# TrinketBlinkM0D.net
KiCad netlist of a schematic drawn in EAGLE
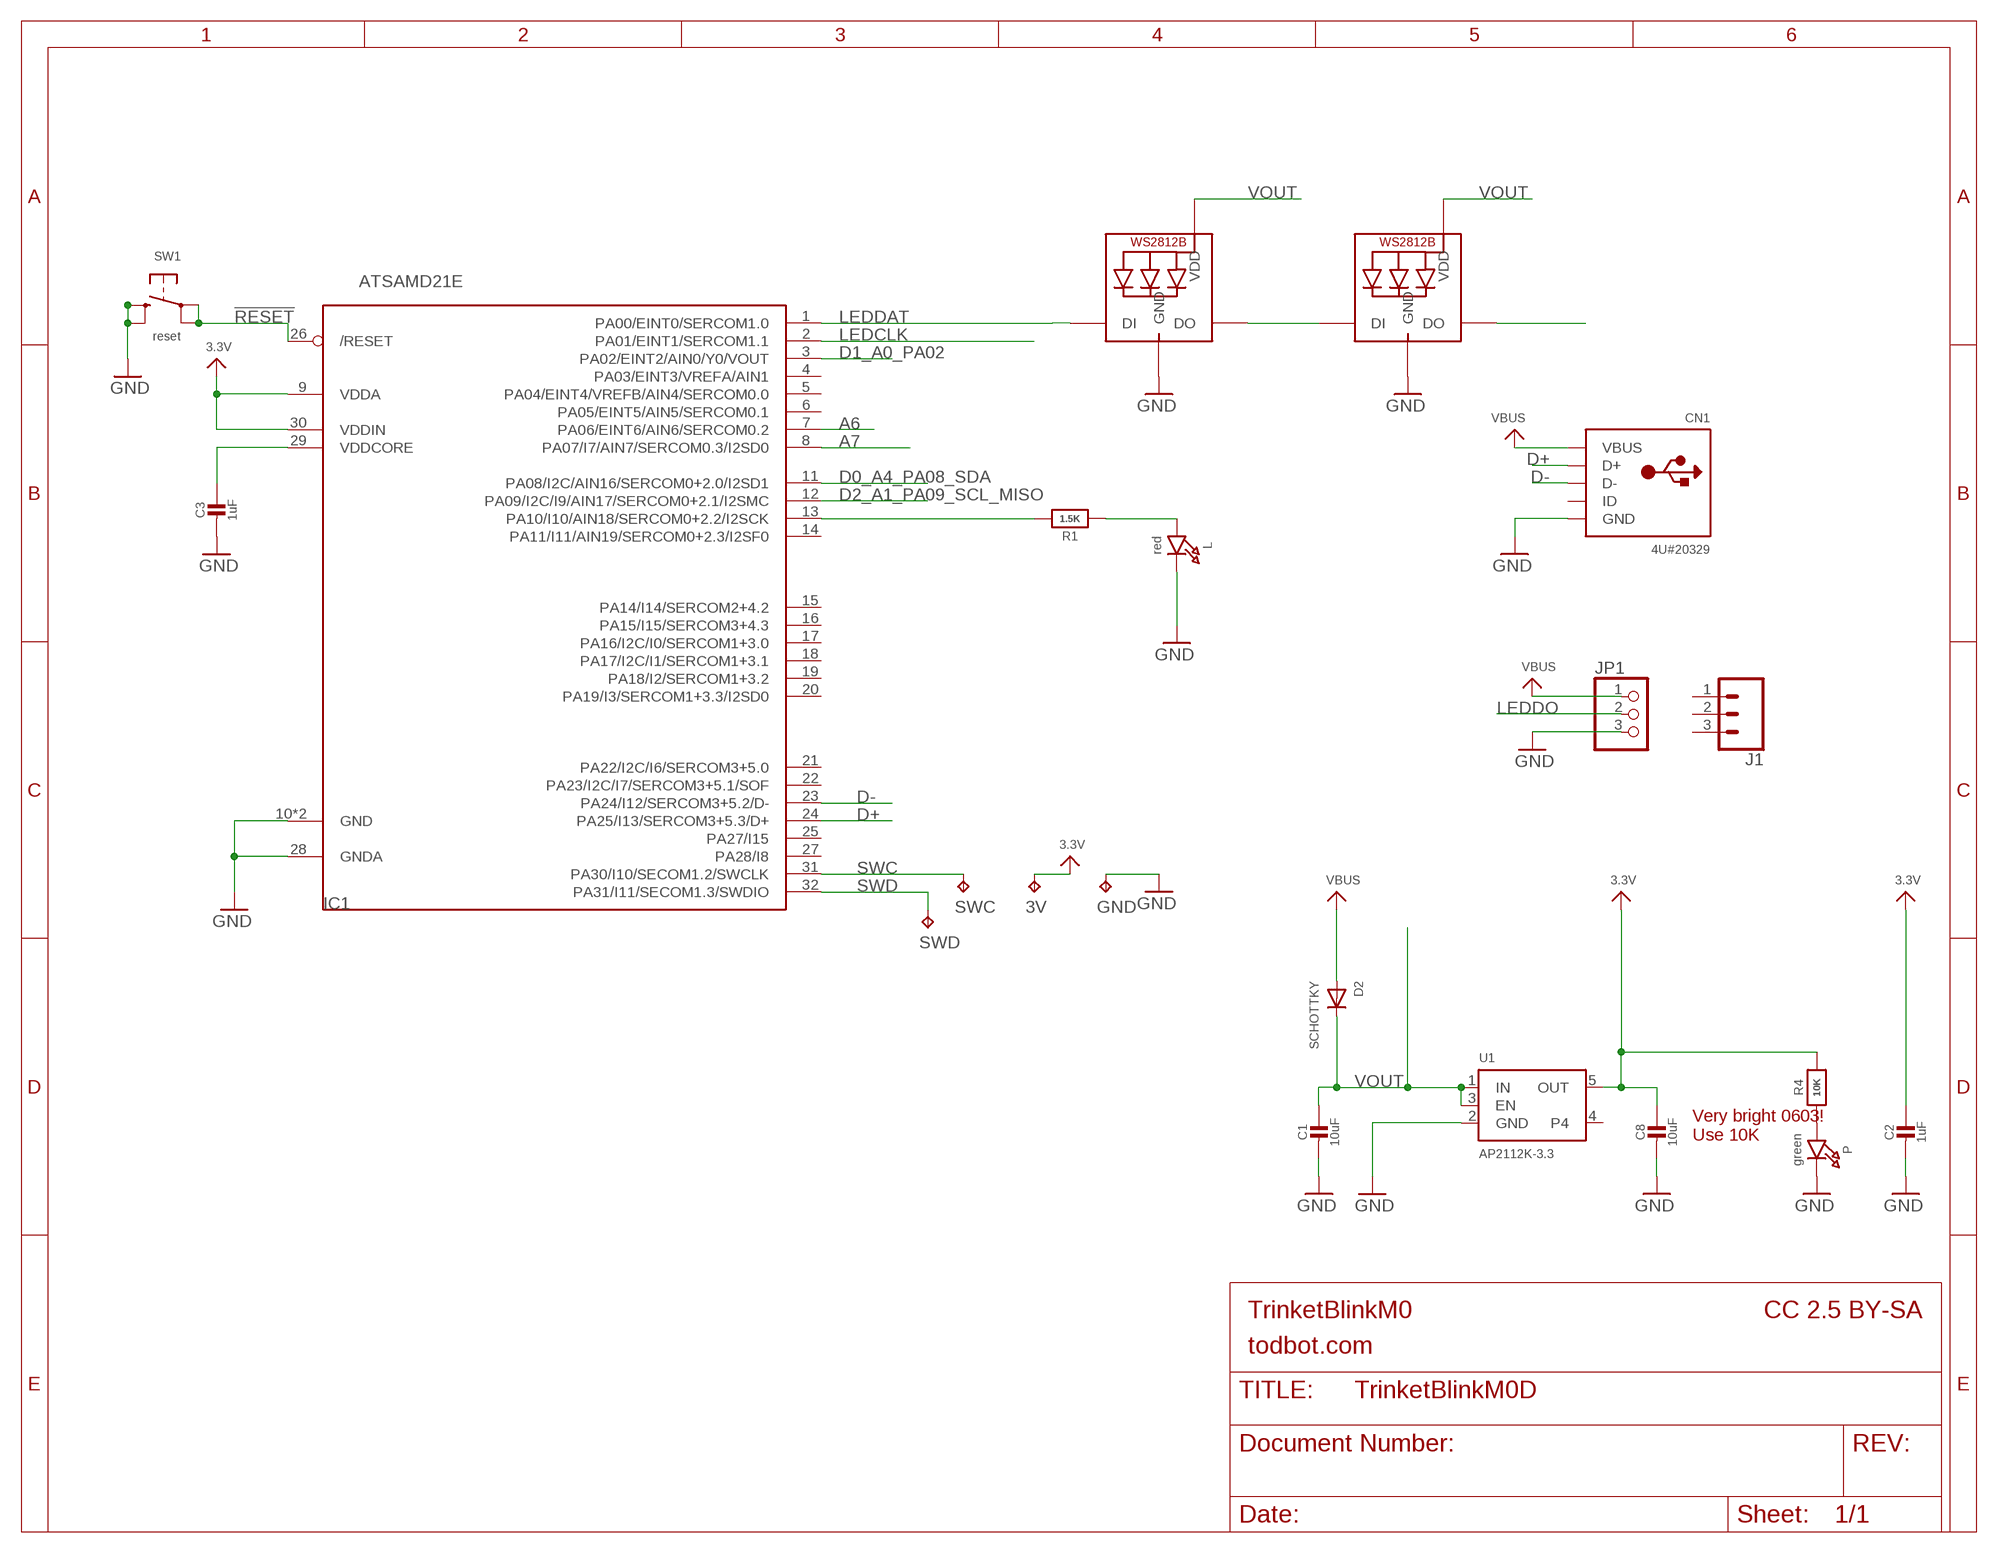
[diagram p0: schematic, sheet 1]

(export (version "E")
  (design (tool "Eeschema 10.0.6"))
  (components
    (comp (ref "3V")
      (value "TPB1,27")
      (footprint "eagle-import:B1,27")
      (libsource (lib "eagle-import") (part "TPB1,27"))
    )
    (comp (ref "C1")
      (value "10uF")
      (footprint "eagle-import:0805-NO")
      (libsource (lib "eagle-import") (part "CAP_CERAMIC0805-NOOUTLINE"))
    )
    (comp (ref "C2")
      (value "1uF")
      (footprint "eagle-import:0603-NO")
      (libsource (lib "eagle-import") (part "CAP_CERAMIC0603_NO"))
    )
    (comp (ref "C3")
      (value "1uF")
      (footprint "eagle-import:0603-NO")
      (libsource (lib "eagle-import") (part "CAP_CERAMIC0603_NO"))
    )
    (comp (ref "C8")
      (value "10uF")
      (footprint "eagle-import:0805-NO")
      (libsource (lib "eagle-import") (part "CAP_CERAMIC0805-NOOUTLINE"))
    )
    (comp (ref "CN1")
      (value "4U#20329")
      (footprint "eagle-import:4UCONN_20329_V2")
      (libsource (lib "eagle-import") (part "USB_MICRO_20329_V2"))
    )
    (comp (ref "D2")
      (value "SCHOTTKY")
      (footprint "eagle-import:SOD-123FL")
      (libsource (lib "eagle-import") (part "DIODE_SOD-123FL"))
    )
    (comp (ref "GND")
      (value "TPB1,27")
      (footprint "eagle-import:B1,27")
      (libsource (lib "eagle-import") (part "TPB1,27"))
    )
    (comp (ref "IC1")
      (value "ATSAMD21E")
      (footprint "eagle-import:QFN32_5MM")
      (libsource (lib "eagle-import") (part "ATSAMD21E"))
    )
    (comp (ref "J1")
      (value "CONN_03LONGPADS")
      (footprint "eagle-import:1X03_LONGPADS")
      (libsource (lib "eagle-import") (part "CONN_03LONGPADS"))
    )
    (comp (ref "JP1")
      (value "PINHD-1X3CB")
      (footprint "eagle-import:1X03-CLEANBIG")
      (libsource (lib "eagle-import") (part "PINHD-1X3CB"))
    )
    (comp (ref "L")
      (value "red")
      (footprint "eagle-import:CHIPLED_0603_NOOUTLINE")
      (libsource (lib "eagle-import") (part "LED0603_NOOUTLINE"))
    )
    (comp (ref "LED1")
      (value "WS2812B_5050N")
      (footprint "eagle-import:WS2812B-NARROW")
      (libsource (lib "eagle-import") (part "WS2812B_5050N"))
    )
    (comp (ref "LED2")
      (value "WS2812B_5050N")
      (footprint "eagle-import:WS2812B-NARROW")
      (libsource (lib "eagle-import") (part "WS2812B_5050N"))
    )
    (comp (ref "P")
      (value "green")
      (footprint "eagle-import:CHIPLED_0603_NOOUTLINE")
      (libsource (lib "eagle-import") (part "LED0603_NOOUTLINE"))
    )
    (comp (ref "R1")
      (value "1.5K")
      (footprint "eagle-import:0603-NO")
      (libsource (lib "eagle-import") (part "RESISTOR_0603_NOOUT"))
    )
    (comp (ref "R4")
      (value "10K")
      (footprint "eagle-import:0603-NO")
      (libsource (lib "eagle-import") (part "RESISTOR_0603_NOOUT"))
    )
    (comp (ref "SW1")
      (value "reset")
      (footprint "eagle-import:BTN_KMR2_4.6X2.8")
      (libsource (lib "eagle-import") (part "SWITCH_TACT_SMT4.6X2.8"))
    )
    (comp (ref "SWC")
      (value "TPB1,27")
      (footprint "eagle-import:B1,27")
      (libsource (lib "eagle-import") (part "TPB1,27"))
    )
    (comp (ref "SWD")
      (value "TPB1,27")
      (footprint "eagle-import:B1,27")
      (libsource (lib "eagle-import") (part "TPB1,27"))
    )
    (comp (ref "U1")
      (value "AP2112K-3.3")
      (footprint "eagle-import:SOT23-5")
      (libsource (lib "eagle-import") (part "VREG_SOT23-5"))
    )
  )
  (nets
    (net (code "1") (name "/A6") (class "Default")
      (node (ref "IC1") (pin "7") (pinfunction "PA06/EINT6/AIN6/SERCOM0.2_7") (pintype "bidirectional"))
    )
    (net (code "2") (name "/A7") (class "Default")
      (node (ref "IC1") (pin "8") (pinfunction "PA07/I7/AIN7/SERCOM0.3/I2SD0_8") (pintype "bidirectional"))
    )
    (net (code "3") (name "/D+") (class "Default")
      (node (ref "CN1") (pin "D+") (pinfunction "D+_D+") (pintype "bidirectional"))
      (node (ref "IC1") (pin "24") (pinfunction "PA25/I13/SERCOM3+5.3/D+_24") (pintype "bidirectional"))
    )
    (net (code "4") (name "/D-") (class "Default")
      (node (ref "CN1") (pin "D-") (pinfunction "D-_D-") (pintype "bidirectional"))
      (node (ref "IC1") (pin "23") (pinfunction "PA24/I12/SERCOM3+5.2/D-_23") (pintype "bidirectional"))
    )
    (net (code "5") (name "/D0_A4_PA08_SDA") (class "Default")
      (node (ref "IC1") (pin "11") (pinfunction "PA08/I2C/AIN16/SERCOM0+2.0/I2SD1_11") (pintype "bidirectional"))
    )
    (net (code "6") (name "/D1_A0_PA02") (class "Default")
      (node (ref "IC1") (pin "3") (pinfunction "PA02/EINT2/AIN0/Y0/VOUT_3") (pintype "bidirectional"))
    )
    (net (code "7") (name "/D2_A1_PA09_SCL_MISO") (class "Default")
      (node (ref "IC1") (pin "12") (pinfunction "PA09/I2C/I9/AIN17/SERCOM0+2.1/I2SMC_12") (pintype "bidirectional"))
    )
    (net (code "8") (name "/LEDCLK") (class "Default")
      (node (ref "IC1") (pin "2") (pinfunction "PA01/EINT1/SERCOM1.1_2") (pintype "bidirectional"))
    )
    (net (code "9") (name "/LEDDAT") (class "Default")
      (node (ref "IC1") (pin "1") (pinfunction "PA00/EINT0/SERCOM1.0_1") (pintype "bidirectional"))
      (node (ref "LED1") (pin "4-DIN") (pinfunction "DI_4-DIN") (pintype "input"))
    )
    (net (code "10") (name "/LEDDO") (class "Default")
      (node (ref "JP1") (pin "2") (pinfunction "2_2") (pintype "passive"))
      (node (ref "LED2") (pin "2-DOUT") (pinfunction "DO_2-DOUT") (pintype "output"))
    )
    (net (code "11") (name "/SWC") (class "Default")
      (node (ref "IC1") (pin "31") (pinfunction "PA30/I10/SECOM1.2/SWCLK_31") (pintype "bidirectional"))
      (node (ref "SWC") (pin "TP") (pinfunction "TP_TP") (pintype "input"))
    )
    (net (code "12") (name "/SWD") (class "Default")
      (node (ref "IC1") (pin "32") (pinfunction "PA31/I11/SECOM1.3/SWDIO_32") (pintype "bidirectional"))
      (node (ref "SWD") (pin "TP") (pinfunction "TP_TP") (pintype "input"))
    )
    (net (code "13") (name "/VOUT") (class "Default")
      (node (ref "C1") (pin "1") (pinfunction "1_1") (pintype "passive"))
      (node (ref "D2") (pin "C") (pinfunction "C_C") (pintype "passive"))
      (node (ref "LED1") (pin "1-VDD") (pinfunction "VDD_1-VDD") (pintype "power_in"))
      (node (ref "LED2") (pin "1-VDD") (pinfunction "VDD_1-VDD") (pintype "power_in"))
      (node (ref "U1") (pin "1") (pinfunction "IN_1") (pintype "power_in"))
      (node (ref "U1") (pin "3") (pinfunction "EN_3") (pintype "input"))
    )
    (net (code "14") (name "/~{RESET}") (class "Default")
      (node (ref "IC1") (pin "26") (pinfunction "/RESET_26") (pintype "bidirectional"))
      (node (ref "SW1") (pin "A") (pinfunction "P_A") (pintype "passive"))
      (node (ref "SW1") (pin "A'") (pinfunction "P1_A'") (pintype "passive"))
    )
    (net (code "15") (name "3.3V") (class "Default")
      (node (ref "3V") (pin "TP") (pinfunction "TP_TP") (pintype "input"))
      (node (ref "C2") (pin "1") (pinfunction "1_1") (pintype "passive"))
      (node (ref "C8") (pin "1") (pinfunction "1_1") (pintype "passive"))
      (node (ref "IC1") (pin "30") (pinfunction "VDDIN_30") (pintype "power_in"))
      (node (ref "IC1") (pin "9") (pinfunction "VDDA_9") (pintype "power_in"))
      (node (ref "R4") (pin "2") (pinfunction "2_2") (pintype "passive"))
      (node (ref "U1") (pin "5") (pinfunction "OUT_5") (pintype "power_in"))
    )
    (net (code "16") (name "GND") (class "Default")
      (node (ref "C1") (pin "2") (pinfunction "2_2") (pintype "passive"))
      (node (ref "C2") (pin "2") (pinfunction "2_2") (pintype "passive"))
      (node (ref "C3") (pin "2") (pinfunction "2_2") (pintype "passive"))
      (node (ref "C8") (pin "2") (pinfunction "2_2") (pintype "passive"))
      (node (ref "CN1") (pin "BASE@1") (pinfunction "GND_BASE@1") (pintype "power_in"))
      (node (ref "CN1") (pin "BASE@2") (pinfunction "GND_BASE@2") (pintype "power_in"))
      (node (ref "CN1") (pin "GND") (pinfunction "GND_GND") (pintype "power_in"))
      (node (ref "CN1") (pin "SPRT@1") (pinfunction "GND_SPRT@1") (pintype "power_in"))
      (node (ref "CN1") (pin "SPRT@2") (pinfunction "GND_SPRT@2") (pintype "power_in"))
      (node (ref "CN1") (pin "SPRT@3") (pinfunction "GND_SPRT@3") (pintype "power_in"))
      (node (ref "CN1") (pin "SPRT@4") (pinfunction "GND_SPRT@4") (pintype "power_in"))
      (node (ref "GND") (pin "TP") (pinfunction "TP_TP") (pintype "input"))
      (node (ref "IC1") (pin "10") (pinfunction "GND_10") (pintype "power_in"))
      (node (ref "IC1") (pin "28") (pinfunction "GNDA_28") (pintype "power_in"))
      (node (ref "IC1") (pin "33") (pinfunction "GND_33") (pintype "power_in"))
      (node (ref "JP1") (pin "3") (pinfunction "3_3") (pintype "passive"))
      (node (ref "L") (pin "C") (pinfunction "C_C") (pintype "passive"))
      (node (ref "LED1") (pin "3-GND") (pinfunction "GND_3-GND") (pintype "power_in"))
      (node (ref "LED2") (pin "3-GND") (pinfunction "GND_3-GND") (pintype "power_in"))
      (node (ref "P") (pin "C") (pinfunction "C_C") (pintype "passive"))
      (node (ref "SW1") (pin "B") (pinfunction "S_B") (pintype "passive"))
      (node (ref "SW1") (pin "B'") (pinfunction "S1_B'") (pintype "passive"))
      (node (ref "U1") (pin "2") (pinfunction "GND_2") (pintype "power_in"))
    )
    (net (code "17") (name "Net-(IC1-PA10{slash}I10{slash}AIN18{slash}SERCOM0+2.2{slash}I2SCK)") (class "Default")
      (node (ref "IC1") (pin "13") (pinfunction "PA10/I10/AIN18/SERCOM0+2.2/I2SCK_13") (pintype "bidirectional"))
      (node (ref "R1") (pin "2") (pinfunction "2_2") (pintype "passive"))
    )
    (net (code "18") (name "Net-(IC1-VDDCORE)") (class "Default")
      (node (ref "C3") (pin "1") (pinfunction "1_1") (pintype "passive"))
      (node (ref "IC1") (pin "29") (pinfunction "VDDCORE_29") (pintype "power_in"))
    )
    (net (code "19") (name "Net-(L-PadA)") (class "Default")
      (node (ref "L") (pin "A") (pinfunction "A_A") (pintype "passive"))
      (node (ref "R1") (pin "1") (pinfunction "1_1") (pintype "passive"))
    )
    (net (code "20") (name "Net-(LED1-DO)") (class "Default")
      (node (ref "LED1") (pin "2-DOUT") (pinfunction "DO_2-DOUT") (pintype "output"))
      (node (ref "LED2") (pin "4-DIN") (pinfunction "DI_4-DIN") (pintype "input"))
    )
    (net (code "21") (name "Net-(P-PadA)") (class "Default")
      (node (ref "P") (pin "A") (pinfunction "A_A") (pintype "passive"))
      (node (ref "R4") (pin "1") (pinfunction "1_1") (pintype "passive"))
    )
    (net (code "22") (name "VBUS") (class "Default")
      (node (ref "CN1") (pin "VBUS") (pinfunction "VBUS_VBUS") (pintype "power_in"))
      (node (ref "D2") (pin "A") (pinfunction "A_A") (pintype "passive"))
      (node (ref "JP1") (pin "1") (pinfunction "1_1") (pintype "passive"))
    )
    (net (code "23") (name "unconnected-(CN1-PadID)") (class "Default")
      (node (ref "CN1") (pin "ID") (pinfunction "ID_ID") (pintype "bidirectional"))
    )
    (net (code "24") (name "unconnected-(IC1-PA03{slash}EINT3{slash}VREFA{slash}AIN1-Pad4)") (class "Default")
      (node (ref "IC1") (pin "4") (pinfunction "PA03/EINT3/VREFA/AIN1_4") (pintype "bidirectional"))
    )
    (net (code "25") (name "unconnected-(IC1-PA04{slash}EINT4{slash}VREFB{slash}AIN4{slash}SERCOM0.0-Pad5)") (class "Default")
      (node (ref "IC1") (pin "5") (pinfunction "PA04/EINT4/VREFB/AIN4/SERCOM0.0_5") (pintype "bidirectional"))
    )
    (net (code "26") (name "unconnected-(IC1-PA05{slash}EINT5{slash}AIN5{slash}SERCOM0.1-Pad6)") (class "Default")
      (node (ref "IC1") (pin "6") (pinfunction "PA05/EINT5/AIN5/SERCOM0.1_6") (pintype "bidirectional"))
    )
    (net (code "27") (name "unconnected-(IC1-PA11{slash}I11{slash}AIN19{slash}SERCOM0+2.3{slash}I2SF0-Pad14)") (class "Default")
      (node (ref "IC1") (pin "14") (pinfunction "PA11/I11/AIN19/SERCOM0+2.3/I2SF0_14") (pintype "bidirectional"))
    )
    (net (code "28") (name "unconnected-(IC1-PA14{slash}I14{slash}SERCOM2+4.2-Pad15)") (class "Default")
      (node (ref "IC1") (pin "15") (pinfunction "PA14/I14/SERCOM2+4.2_15") (pintype "bidirectional"))
    )
    (net (code "29") (name "unconnected-(IC1-PA15{slash}I15{slash}SERCOM3+4.3-Pad16)") (class "Default")
      (node (ref "IC1") (pin "16") (pinfunction "PA15/I15/SERCOM3+4.3_16") (pintype "bidirectional"))
    )
    (net (code "30") (name "unconnected-(IC1-PA16{slash}I2C{slash}I0{slash}SERCOM1+3.0-Pad17)") (class "Default")
      (node (ref "IC1") (pin "17") (pinfunction "PA16/I2C/I0/SERCOM1+3.0_17") (pintype "bidirectional"))
    )
    (net (code "31") (name "unconnected-(IC1-PA17{slash}I2C{slash}I1{slash}SERCOM1+3.1-Pad18)") (class "Default")
      (node (ref "IC1") (pin "18") (pinfunction "PA17/I2C/I1/SERCOM1+3.1_18") (pintype "bidirectional"))
    )
    (net (code "32") (name "unconnected-(IC1-PA18{slash}I2{slash}SERCOM1+3.2-Pad19)") (class "Default")
      (node (ref "IC1") (pin "19") (pinfunction "PA18/I2/SERCOM1+3.2_19") (pintype "bidirectional"))
    )
    (net (code "33") (name "unconnected-(IC1-PA19{slash}I3{slash}SERCOM1+3.3{slash}I2SD0-Pad20)") (class "Default")
      (node (ref "IC1") (pin "20") (pinfunction "PA19/I3/SERCOM1+3.3/I2SD0_20") (pintype "bidirectional"))
    )
    (net (code "34") (name "unconnected-(IC1-PA22{slash}I2C{slash}I6{slash}SERCOM3+5.0-Pad21)") (class "Default")
      (node (ref "IC1") (pin "21") (pinfunction "PA22/I2C/I6/SERCOM3+5.0_21") (pintype "bidirectional"))
    )
    (net (code "35") (name "unconnected-(IC1-PA23{slash}I2C{slash}I7{slash}SERCOM3+5.1{slash}SOF-Pad22)") (class "Default")
      (node (ref "IC1") (pin "22") (pinfunction "PA23/I2C/I7/SERCOM3+5.1/SOF_22") (pintype "bidirectional"))
    )
    (net (code "36") (name "unconnected-(IC1-PA27{slash}I15-Pad25)") (class "Default")
      (node (ref "IC1") (pin "25") (pinfunction "PA27/I15_25") (pintype "bidirectional"))
    )
    (net (code "37") (name "unconnected-(IC1-PA28{slash}I8-Pad27)") (class "Default")
      (node (ref "IC1") (pin "27") (pinfunction "PA28/I8_27") (pintype "bidirectional"))
    )
    (net (code "38") (name "unconnected-(J1-Pad1)") (class "Default")
      (node (ref "J1") (pin "1") (pinfunction "1_1") (pintype "passive"))
    )
    (net (code "39") (name "unconnected-(J1-Pad2)") (class "Default")
      (node (ref "J1") (pin "2") (pinfunction "2_2") (pintype "passive"))
    )
    (net (code "40") (name "unconnected-(J1-Pad3)") (class "Default")
      (node (ref "J1") (pin "3") (pinfunction "3_3") (pintype "passive"))
    )
    (net (code "41") (name "unconnected-(U1-P4-Pad4)") (class "Default")
      (node (ref "U1") (pin "4") (pinfunction "P4_4") (pintype "bidirectional"))
    )
  )
)
